# ProPrj_Motorcycle_Controller_2026-08-27.net
KiCad netlist of a schematic drawn in EasyEDA Pro
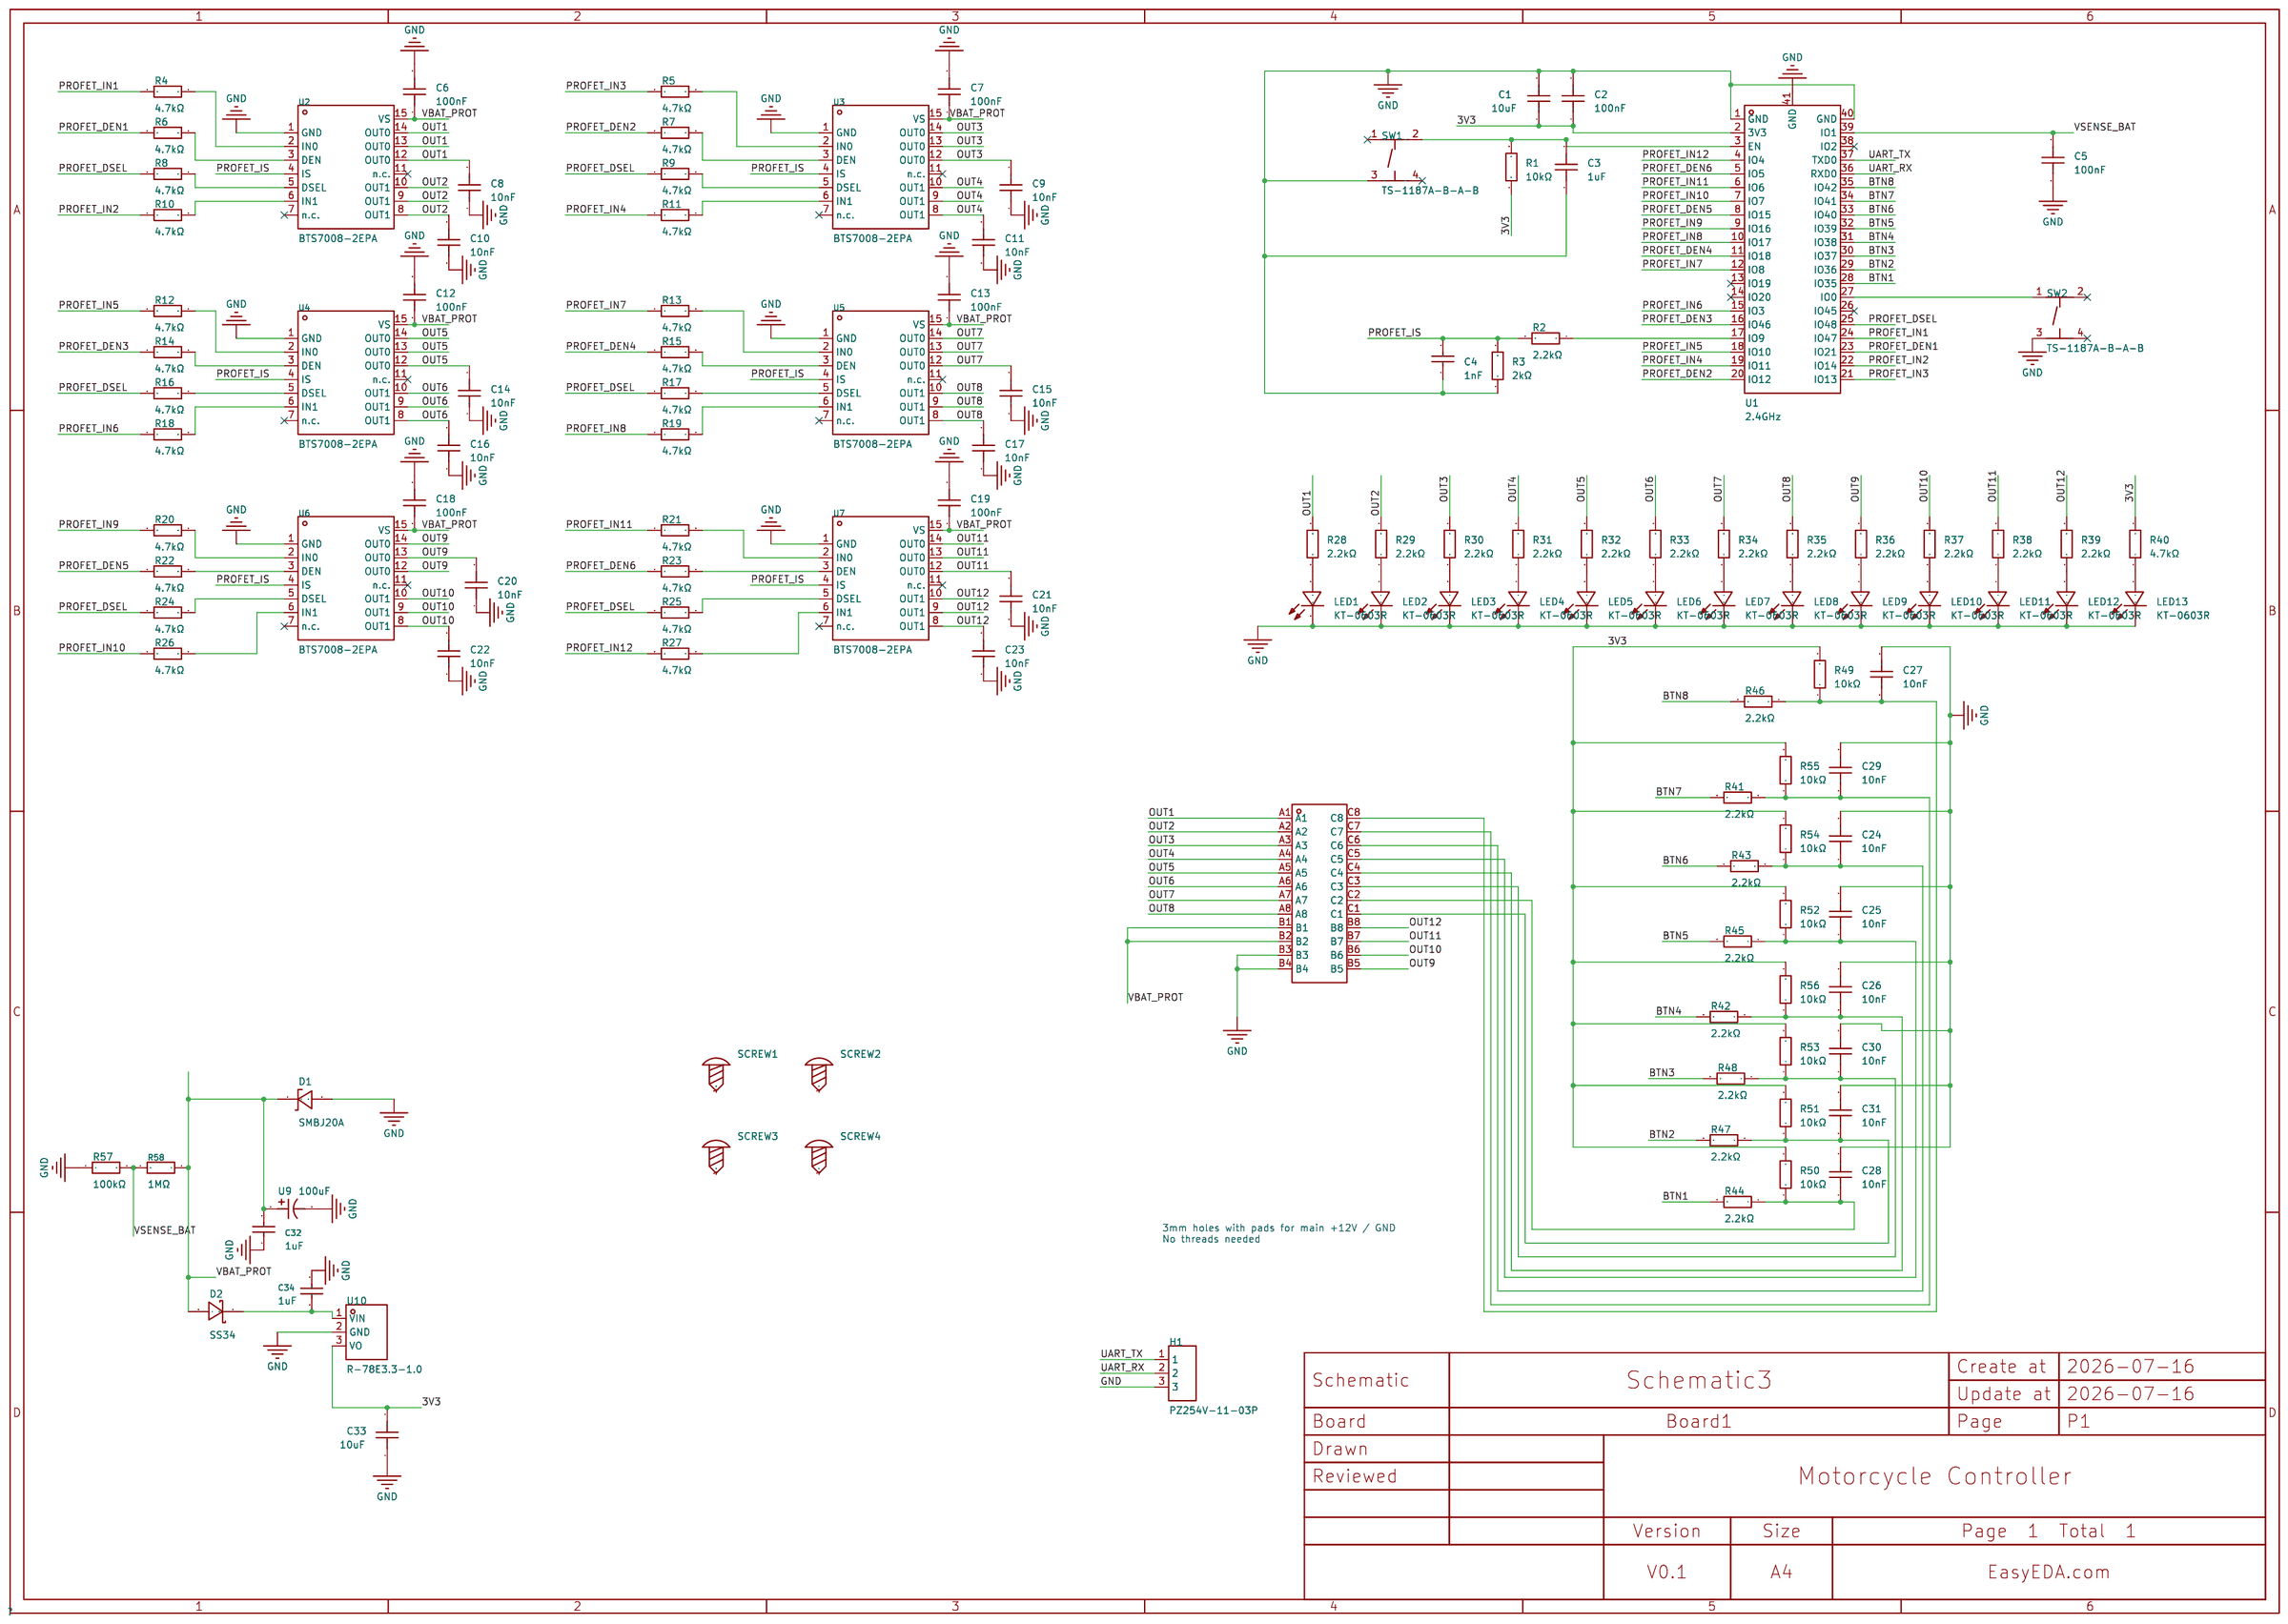
[diagram p0: schematic sheet]

(export (version "E")
  (design (tool "Eeschema 10.0.6"))
  (components
    (comp (ref "C1")
      (value "10uF")
      (footprint "easyedapro:C0603")
      (fields
        (field (name "Manufacturer Part") "CL10A106KP8NNNC")
        (field (name "Manufacturer") "SAMSUNG(三星)")
      )
      (libsource (lib "easyedapro") (part "CL10A106KP8NNNC"))
    )
    (comp (ref "C2")
      (value "100nF")
      (footprint "easyedapro:C0402")
      (fields
        (field (name "Manufacturer Part") "CL05B104KO5NNNC")
        (field (name "Manufacturer") "SAMSUNG(三星)")
      )
      (libsource (lib "easyedapro") (part "CL05B104KO5NNNC"))
    )
    (comp (ref "C3")
      (value "1uF")
      (footprint "easyedapro:C0402")
      (fields
        (field (name "Manufacturer Part") "CL05A105KA5NQNC")
        (field (name "Manufacturer") "SAMSUNG(三星)")
      )
      (libsource (lib "easyedapro") (part "CL05A105KA5NQNC"))
    )
    (comp (ref "C4")
      (value "1nF")
      (footprint "easyedapro:C0402")
      (fields (field (name "Manufacturer Part") "0402B102K500NT") (field (name "Manufacturer") "FH(风华)"))
      (libsource (lib "easyedapro") (part "0402B102K500NT"))
    )
    (comp (ref "C5")
      (value "100nF")
      (footprint "easyedapro:C0402")
      (fields
        (field (name "Manufacturer Part") "CL05B104KO5NNNC")
        (field (name "Manufacturer") "SAMSUNG(三星)")
      )
      (libsource (lib "easyedapro") (part "CL05B104KO5NNNC"))
    )
    (comp (ref "C6")
      (value "100nF")
      (footprint "easyedapro:C0603")
      (fields
        (field (name "Manufacturer Part") "CC0603KRX7R9BB104")
        (field (name "Manufacturer") "YAGEO(国巨)")
      )
      (libsource (lib "easyedapro") (part "CC0603KRX7R9BB104"))
    )
    (comp (ref "C7")
      (value "100nF")
      (footprint "easyedapro:C0603")
      (fields
        (field (name "Manufacturer Part") "CC0603KRX7R9BB104")
        (field (name "Manufacturer") "YAGEO(国巨)")
      )
      (libsource (lib "easyedapro") (part "CC0603KRX7R9BB104"))
    )
    (comp (ref "C8")
      (value "10nF")
      (footprint "easyedapro:C0603")
      (fields (field (name "Manufacturer Part") "0603B103K500NT") (field (name "Manufacturer") "FH(风华)"))
      (libsource (lib "easyedapro") (part "0603B103K500NT"))
    )
    (comp (ref "C9")
      (value "10nF")
      (footprint "easyedapro:C0603")
      (fields (field (name "Manufacturer Part") "0603B103K500NT") (field (name "Manufacturer") "FH(风华)"))
      (libsource (lib "easyedapro") (part "0603B103K500NT"))
    )
    (comp (ref "C10")
      (value "10nF")
      (footprint "easyedapro:C0603")
      (fields (field (name "Manufacturer Part") "0603B103K500NT") (field (name "Manufacturer") "FH(风华)"))
      (libsource (lib "easyedapro") (part "0603B103K500NT"))
    )
    (comp (ref "C11")
      (value "10nF")
      (footprint "easyedapro:C0603")
      (fields (field (name "Manufacturer Part") "0603B103K500NT") (field (name "Manufacturer") "FH(风华)"))
      (libsource (lib "easyedapro") (part "0603B103K500NT"))
    )
    (comp (ref "C12")
      (value "100nF")
      (footprint "easyedapro:C0603")
      (fields
        (field (name "Manufacturer Part") "CC0603KRX7R9BB104")
        (field (name "Manufacturer") "YAGEO(国巨)")
      )
      (libsource (lib "easyedapro") (part "CC0603KRX7R9BB104"))
    )
    (comp (ref "C13")
      (value "100nF")
      (footprint "easyedapro:C0603")
      (fields
        (field (name "Manufacturer Part") "CC0603KRX7R9BB104")
        (field (name "Manufacturer") "YAGEO(国巨)")
      )
      (libsource (lib "easyedapro") (part "CC0603KRX7R9BB104"))
    )
    (comp (ref "C14")
      (value "10nF")
      (footprint "easyedapro:C0603")
      (fields (field (name "Manufacturer Part") "0603B103K500NT") (field (name "Manufacturer") "FH(风华)"))
      (libsource (lib "easyedapro") (part "0603B103K500NT"))
    )
    (comp (ref "C15")
      (value "10nF")
      (footprint "easyedapro:C0603")
      (fields (field (name "Manufacturer Part") "0603B103K500NT") (field (name "Manufacturer") "FH(风华)"))
      (libsource (lib "easyedapro") (part "0603B103K500NT"))
    )
    (comp (ref "C16")
      (value "10nF")
      (footprint "easyedapro:C0603")
      (fields (field (name "Manufacturer Part") "0603B103K500NT") (field (name "Manufacturer") "FH(风华)"))
      (libsource (lib "easyedapro") (part "0603B103K500NT"))
    )
    (comp (ref "C17")
      (value "10nF")
      (footprint "easyedapro:C0603")
      (fields (field (name "Manufacturer Part") "0603B103K500NT") (field (name "Manufacturer") "FH(风华)"))
      (libsource (lib "easyedapro") (part "0603B103K500NT"))
    )
    (comp (ref "C18")
      (value "100nF")
      (footprint "easyedapro:C0603")
      (fields
        (field (name "Manufacturer Part") "CC0603KRX7R9BB104")
        (field (name "Manufacturer") "YAGEO(国巨)")
      )
      (libsource (lib "easyedapro") (part "CC0603KRX7R9BB104"))
    )
    (comp (ref "C19")
      (value "100nF")
      (footprint "easyedapro:C0603")
      (fields
        (field (name "Manufacturer Part") "CC0603KRX7R9BB104")
        (field (name "Manufacturer") "YAGEO(国巨)")
      )
      (libsource (lib "easyedapro") (part "CC0603KRX7R9BB104"))
    )
    (comp (ref "C20")
      (value "10nF")
      (footprint "easyedapro:C0603")
      (fields (field (name "Manufacturer Part") "0603B103K500NT") (field (name "Manufacturer") "FH(风华)"))
      (libsource (lib "easyedapro") (part "0603B103K500NT"))
    )
    (comp (ref "C21")
      (value "10nF")
      (footprint "easyedapro:C0603")
      (fields (field (name "Manufacturer Part") "0603B103K500NT") (field (name "Manufacturer") "FH(风华)"))
      (libsource (lib "easyedapro") (part "0603B103K500NT"))
    )
    (comp (ref "C22")
      (value "10nF")
      (footprint "easyedapro:C0603")
      (fields (field (name "Manufacturer Part") "0603B103K500NT") (field (name "Manufacturer") "FH(风华)"))
      (libsource (lib "easyedapro") (part "0603B103K500NT"))
    )
    (comp (ref "C23")
      (value "10nF")
      (footprint "easyedapro:C0603")
      (fields (field (name "Manufacturer Part") "0603B103K500NT") (field (name "Manufacturer") "FH(风华)"))
      (libsource (lib "easyedapro") (part "0603B103K500NT"))
    )
    (comp (ref "C24")
      (value "10nF")
      (footprint "easyedapro:C0603")
      (fields (field (name "Manufacturer Part") "0603B103K500NT") (field (name "Manufacturer") "FH(风华)"))
      (libsource (lib "easyedapro") (part "0603B103K500NT"))
    )
    (comp (ref "C25")
      (value "10nF")
      (footprint "easyedapro:C0603")
      (fields (field (name "Manufacturer Part") "0603B103K500NT") (field (name "Manufacturer") "FH(风华)"))
      (libsource (lib "easyedapro") (part "0603B103K500NT"))
    )
    (comp (ref "C26")
      (value "10nF")
      (footprint "easyedapro:C0603")
      (fields (field (name "Manufacturer Part") "0603B103K500NT") (field (name "Manufacturer") "FH(风华)"))
      (libsource (lib "easyedapro") (part "0603B103K500NT"))
    )
    (comp (ref "C27")
      (value "10nF")
      (footprint "easyedapro:C0603")
      (fields (field (name "Manufacturer Part") "0603B103K500NT") (field (name "Manufacturer") "FH(风华)"))
      (libsource (lib "easyedapro") (part "0603B103K500NT"))
    )
    (comp (ref "C28")
      (value "10nF")
      (footprint "easyedapro:C0603")
      (fields (field (name "Manufacturer Part") "0603B103K500NT") (field (name "Manufacturer") "FH(风华)"))
      (libsource (lib "easyedapro") (part "0603B103K500NT"))
    )
    (comp (ref "C29")
      (value "10nF")
      (footprint "easyedapro:C0603")
      (fields (field (name "Manufacturer Part") "0603B103K500NT") (field (name "Manufacturer") "FH(风华)"))
      (libsource (lib "easyedapro") (part "0603B103K500NT"))
    )
    (comp (ref "C30")
      (value "10nF")
      (footprint "easyedapro:C0603")
      (fields (field (name "Manufacturer Part") "0603B103K500NT") (field (name "Manufacturer") "FH(风华)"))
      (libsource (lib "easyedapro") (part "0603B103K500NT"))
    )
    (comp (ref "C31")
      (value "10nF")
      (footprint "easyedapro:C0603")
      (fields (field (name "Manufacturer Part") "0603B103K500NT") (field (name "Manufacturer") "FH(风华)"))
      (libsource (lib "easyedapro") (part "0603B103K500NT"))
    )
    (comp (ref "C32")
      (value "1uF")
      (footprint "easyedapro:C0805")
      (fields
        (field (name "Manufacturer Part") "CL21B105KBFNNNE")
        (field (name "Manufacturer") "SAMSUNG(三星)")
      )
      (libsource (lib "easyedapro") (part "CL21B105KBFNNNE"))
    )
    (comp (ref "C33")
      (value "10uF")
      (footprint "easyedapro:C0603")
      (fields
        (field (name "Manufacturer Part") "CL10A106KP8NNNC")
        (field (name "Manufacturer") "SAMSUNG(三星)")
      )
      (libsource (lib "easyedapro") (part "CL10A106KP8NNNC"))
    )
    (comp (ref "C34")
      (value "1uF")
      (footprint "easyedapro:C0805")
      (fields
        (field (name "Manufacturer Part") "CL21B105KBFNNNE")
        (field (name "Manufacturer") "SAMSUNG(三星)")
      )
      (libsource (lib "easyedapro") (part "CL21B105KBFNNNE"))
    )
    (comp (ref "CN3")
      (value "HCCPHPE24BKA90F")
      (footprint "easyedapro:CONN-TH_HCCPHPE24BKA90F")
      (fields (field (name "Manufacturer") "Aptiv(Delphi)"))
      (libsource (lib "easyedapro") (part "HCCPHPE24BKA90F_C5349068"))
    )
    (comp (ref "D1")
      (value "SMBJ20A")
      (footprint "easyedapro:SMB_L4.6-W3.6-LS5.3-RD")
      (fields (field (name "Manufacturer") "MDD(辰达半导体)"))
      (libsource (lib "easyedapro") (part "SMBJ20A_C364296"))
    )
    (comp (ref "D2")
      (value "SS34")
      (footprint "easyedapro:SMA_L4.3-W2.6-LS5.2-RD")
      (fields (field (name "Manufacturer") "MDD(辰达半导体)"))
      (libsource (lib "easyedapro") (part "SS34_C8678"))
    )
    (comp (ref "H1")
      (value "PZ254V-11-03P")
      (footprint "easyedapro:HDR-TH_3P-P2.54-V-M_PZ254V-11-03P")
      (fields (field (name "Manufacturer") "XFCN(兴飞)"))
      (libsource (lib "easyedapro") (part "PZ254V-11-03P_C2937625"))
    )
    (comp (ref "LED1")
      (value "KT-0603R")
      (footprint "easyedapro:LED-SMD_L1.6-W0.8-R-RD")
      (fields (field (name "Manufacturer") "KENTO"))
      (libsource (lib "easyedapro") (part "KT-0603R"))
    )
    (comp (ref "LED2")
      (value "KT-0603R")
      (footprint "easyedapro:LED-SMD_L1.6-W0.8-R-RD")
      (fields (field (name "Manufacturer") "KENTO"))
      (libsource (lib "easyedapro") (part "KT-0603R"))
    )
    (comp (ref "LED3")
      (value "KT-0603R")
      (footprint "easyedapro:LED-SMD_L1.6-W0.8-R-RD")
      (fields (field (name "Manufacturer") "KENTO"))
      (libsource (lib "easyedapro") (part "KT-0603R"))
    )
    (comp (ref "LED4")
      (value "KT-0603R")
      (footprint "easyedapro:LED-SMD_L1.6-W0.8-R-RD")
      (fields (field (name "Manufacturer") "KENTO"))
      (libsource (lib "easyedapro") (part "KT-0603R"))
    )
    (comp (ref "LED5")
      (value "KT-0603R")
      (footprint "easyedapro:LED-SMD_L1.6-W0.8-R-RD")
      (fields (field (name "Manufacturer") "KENTO"))
      (libsource (lib "easyedapro") (part "KT-0603R"))
    )
    (comp (ref "LED6")
      (value "KT-0603R")
      (footprint "easyedapro:LED-SMD_L1.6-W0.8-R-RD")
      (fields (field (name "Manufacturer") "KENTO"))
      (libsource (lib "easyedapro") (part "KT-0603R"))
    )
    (comp (ref "LED7")
      (value "KT-0603R")
      (footprint "easyedapro:LED-SMD_L1.6-W0.8-R-RD")
      (fields (field (name "Manufacturer") "KENTO"))
      (libsource (lib "easyedapro") (part "KT-0603R"))
    )
    (comp (ref "LED8")
      (value "KT-0603R")
      (footprint "easyedapro:LED-SMD_L1.6-W0.8-R-RD")
      (fields (field (name "Manufacturer") "KENTO"))
      (libsource (lib "easyedapro") (part "KT-0603R"))
    )
    (comp (ref "LED9")
      (value "KT-0603R")
      (footprint "easyedapro:LED-SMD_L1.6-W0.8-R-RD")
      (fields (field (name "Manufacturer") "KENTO"))
      (libsource (lib "easyedapro") (part "KT-0603R"))
    )
    (comp (ref "LED10")
      (value "KT-0603R")
      (footprint "easyedapro:LED-SMD_L1.6-W0.8-R-RD")
      (fields (field (name "Manufacturer") "KENTO"))
      (libsource (lib "easyedapro") (part "KT-0603R"))
    )
    (comp (ref "LED11")
      (value "KT-0603R")
      (footprint "easyedapro:LED-SMD_L1.6-W0.8-R-RD")
      (fields (field (name "Manufacturer") "KENTO"))
      (libsource (lib "easyedapro") (part "KT-0603R"))
    )
    (comp (ref "LED12")
      (value "KT-0603R")
      (footprint "easyedapro:LED-SMD_L1.6-W0.8-R-RD")
      (fields (field (name "Manufacturer") "KENTO"))
      (libsource (lib "easyedapro") (part "KT-0603R"))
    )
    (comp (ref "LED13")
      (value "KT-0603R")
      (footprint "easyedapro:LED-SMD_L1.6-W0.8-R-RD")
      (fields (field (name "Manufacturer") "KENTO"))
      (libsource (lib "easyedapro") (part "KT-0603R"))
    )
    (comp (ref "R1")
      (value "10kΩ")
      (footprint "easyedapro:R0402")
      (fields (field (name "Manufacturer Part") "RC0402FR-0710KL") (field (name "Manufacturer") "YAGEO(国巨)"))
      (libsource (lib "easyedapro") (part "RC0402FR-0710KL"))
    )
    (comp (ref "R2")
      (value "2.2kΩ")
      (footprint "easyedapro:R0603")
      (fields
        (field (name "Manufacturer Part") "0603WAF2201T5E")
        (field (name "Manufacturer") "UNI-ROYAL(厚声)")
      )
      (libsource (lib "easyedapro") (part "0603WAF2201T5E"))
    )
    (comp (ref "R3")
      (value "2kΩ")
      (footprint "easyedapro:R0603")
      (fields
        (field (name "Manufacturer Part") "0603WAF2001T5E")
        (field (name "Manufacturer") "UNI-ROYAL(厚声)")
      )
      (libsource (lib "easyedapro") (part "0603WAF2001T5E"))
    )
    (comp (ref "R4")
      (value "4.7kΩ")
      (footprint "easyedapro:R0603")
      (fields
        (field (name "Manufacturer Part") "0603WAF4701T5E")
        (field (name "Manufacturer") "UNI-ROYAL(厚声)")
      )
      (libsource (lib "easyedapro") (part "0603WAF4701T5E"))
    )
    (comp (ref "R5")
      (value "4.7kΩ")
      (footprint "easyedapro:R0603")
      (fields
        (field (name "Manufacturer Part") "0603WAF4701T5E")
        (field (name "Manufacturer") "UNI-ROYAL(厚声)")
      )
      (libsource (lib "easyedapro") (part "0603WAF4701T5E"))
    )
    (comp (ref "R6")
      (value "4.7kΩ")
      (footprint "easyedapro:R0603")
      (fields
        (field (name "Manufacturer Part") "0603WAF4701T5E")
        (field (name "Manufacturer") "UNI-ROYAL(厚声)")
      )
      (libsource (lib "easyedapro") (part "0603WAF4701T5E"))
    )
    (comp (ref "R7")
      (value "4.7kΩ")
      (footprint "easyedapro:R0603")
      (fields
        (field (name "Manufacturer Part") "0603WAF4701T5E")
        (field (name "Manufacturer") "UNI-ROYAL(厚声)")
      )
      (libsource (lib "easyedapro") (part "0603WAF4701T5E"))
    )
    (comp (ref "R8")
      (value "4.7kΩ")
      (footprint "easyedapro:R0603")
      (fields
        (field (name "Manufacturer Part") "0603WAF4701T5E")
        (field (name "Manufacturer") "UNI-ROYAL(厚声)")
      )
      (libsource (lib "easyedapro") (part "0603WAF4701T5E"))
    )
    (comp (ref "R9")
      (value "4.7kΩ")
      (footprint "easyedapro:R0603")
      (fields
        (field (name "Manufacturer Part") "0603WAF4701T5E")
        (field (name "Manufacturer") "UNI-ROYAL(厚声)")
      )
      (libsource (lib "easyedapro") (part "0603WAF4701T5E"))
    )
    (comp (ref "R10")
      (value "4.7kΩ")
      (footprint "easyedapro:R0603")
      (fields
        (field (name "Manufacturer Part") "0603WAF4701T5E")
        (field (name "Manufacturer") "UNI-ROYAL(厚声)")
      )
      (libsource (lib "easyedapro") (part "0603WAF4701T5E"))
    )
    (comp (ref "R11")
      (value "4.7kΩ")
      (footprint "easyedapro:R0603")
      (fields
        (field (name "Manufacturer Part") "0603WAF4701T5E")
        (field (name "Manufacturer") "UNI-ROYAL(厚声)")
      )
      (libsource (lib "easyedapro") (part "0603WAF4701T5E"))
    )
    (comp (ref "R12")
      (value "4.7kΩ")
      (footprint "easyedapro:R0603")
      (fields
        (field (name "Manufacturer Part") "0603WAF4701T5E")
        (field (name "Manufacturer") "UNI-ROYAL(厚声)")
      )
      (libsource (lib "easyedapro") (part "0603WAF4701T5E"))
    )
    (comp (ref "R13")
      (value "4.7kΩ")
      (footprint "easyedapro:R0603")
      (fields
        (field (name "Manufacturer Part") "0603WAF4701T5E")
        (field (name "Manufacturer") "UNI-ROYAL(厚声)")
      )
      (libsource (lib "easyedapro") (part "0603WAF4701T5E"))
    )
    (comp (ref "R14")
      (value "4.7kΩ")
      (footprint "easyedapro:R0603")
      (fields
        (field (name "Manufacturer Part") "0603WAF4701T5E")
        (field (name "Manufacturer") "UNI-ROYAL(厚声)")
      )
      (libsource (lib "easyedapro") (part "0603WAF4701T5E"))
    )
    (comp (ref "R15")
      (value "4.7kΩ")
      (footprint "easyedapro:R0603")
      (fields
        (field (name "Manufacturer Part") "0603WAF4701T5E")
        (field (name "Manufacturer") "UNI-ROYAL(厚声)")
      )
      (libsource (lib "easyedapro") (part "0603WAF4701T5E"))
    )
    (comp (ref "R16")
      (value "4.7kΩ")
      (footprint "easyedapro:R0603")
      (fields
        (field (name "Manufacturer Part") "0603WAF4701T5E")
        (field (name "Manufacturer") "UNI-ROYAL(厚声)")
      )
      (libsource (lib "easyedapro") (part "0603WAF4701T5E"))
    )
    (comp (ref "R17")
      (value "4.7kΩ")
      (footprint "easyedapro:R0603")
      (fields
        (field (name "Manufacturer Part") "0603WAF4701T5E")
        (field (name "Manufacturer") "UNI-ROYAL(厚声)")
      )
      (libsource (lib "easyedapro") (part "0603WAF4701T5E"))
    )
    (comp (ref "R18")
      (value "4.7kΩ")
      (footprint "easyedapro:R0603")
      (fields
        (field (name "Manufacturer Part") "0603WAF4701T5E")
        (field (name "Manufacturer") "UNI-ROYAL(厚声)")
      )
      (libsource (lib "easyedapro") (part "0603WAF4701T5E"))
    )
    (comp (ref "R19")
      (value "4.7kΩ")
      (footprint "easyedapro:R0603")
      (fields
        (field (name "Manufacturer Part") "0603WAF4701T5E")
        (field (name "Manufacturer") "UNI-ROYAL(厚声)")
      )
      (libsource (lib "easyedapro") (part "0603WAF4701T5E"))
    )
    (comp (ref "R20")
      (value "4.7kΩ")
      (footprint "easyedapro:R0603")
      (fields
        (field (name "Manufacturer Part") "0603WAF4701T5E")
        (field (name "Manufacturer") "UNI-ROYAL(厚声)")
      )
      (libsource (lib "easyedapro") (part "0603WAF4701T5E"))
    )
    (comp (ref "R21")
      (value "4.7kΩ")
      (footprint "easyedapro:R0603")
      (fields
        (field (name "Manufacturer Part") "0603WAF4701T5E")
        (field (name "Manufacturer") "UNI-ROYAL(厚声)")
      )
      (libsource (lib "easyedapro") (part "0603WAF4701T5E"))
    )
    (comp (ref "R22")
      (value "4.7kΩ")
      (footprint "easyedapro:R0603")
      (fields
        (field (name "Manufacturer Part") "0603WAF4701T5E")
        (field (name "Manufacturer") "UNI-ROYAL(厚声)")
      )
      (libsource (lib "easyedapro") (part "0603WAF4701T5E"))
    )
    (comp (ref "R23")
      (value "4.7kΩ")
      (footprint "easyedapro:R0603")
      (fields
        (field (name "Manufacturer Part") "0603WAF4701T5E")
        (field (name "Manufacturer") "UNI-ROYAL(厚声)")
      )
      (libsource (lib "easyedapro") (part "0603WAF4701T5E"))
    )
    (comp (ref "R24")
      (value "4.7kΩ")
      (footprint "easyedapro:R0603")
      (fields
        (field (name "Manufacturer Part") "0603WAF4701T5E")
        (field (name "Manufacturer") "UNI-ROYAL(厚声)")
      )
      (libsource (lib "easyedapro") (part "0603WAF4701T5E"))
    )
    (comp (ref "R25")
      (value "4.7kΩ")
      (footprint "easyedapro:R0603")
      (fields
        (field (name "Manufacturer Part") "0603WAF4701T5E")
        (field (name "Manufacturer") "UNI-ROYAL(厚声)")
      )
      (libsource (lib "easyedapro") (part "0603WAF4701T5E"))
    )
    (comp (ref "R26")
      (value "4.7kΩ")
      (footprint "easyedapro:R0603")
      (fields
        (field (name "Manufacturer Part") "0603WAF4701T5E")
        (field (name "Manufacturer") "UNI-ROYAL(厚声)")
      )
      (libsource (lib "easyedapro") (part "0603WAF4701T5E"))
    )
    (comp (ref "R27")
      (value "4.7kΩ")
      (footprint "easyedapro:R0603")
      (fields
        (field (name "Manufacturer Part") "0603WAF4701T5E")
        (field (name "Manufacturer") "UNI-ROYAL(厚声)")
      )
      (libsource (lib "easyedapro") (part "0603WAF4701T5E"))
    )
    (comp (ref "R28")
      (value "2.2kΩ")
      (footprint "easyedapro:R0603")
      (fields
        (field (name "Manufacturer Part") "0603WAF2201T5E")
        (field (name "Manufacturer") "UNI-ROYAL(厚声)")
      )
      (libsource (lib "easyedapro") (part "0603WAF2201T5E"))
    )
    (comp (ref "R29")
      (value "2.2kΩ")
      (footprint "easyedapro:R0603")
      (fields
        (field (name "Manufacturer Part") "0603WAF2201T5E")
        (field (name "Manufacturer") "UNI-ROYAL(厚声)")
      )
      (libsource (lib "easyedapro") (part "0603WAF2201T5E"))
    )
    (comp (ref "R30")
      (value "2.2kΩ")
      (footprint "easyedapro:R0603")
      (fields
        (field (name "Manufacturer Part") "0603WAF2201T5E")
        (field (name "Manufacturer") "UNI-ROYAL(厚声)")
      )
      (libsource (lib "easyedapro") (part "0603WAF2201T5E"))
    )
    (comp (ref "R31")
      (value "2.2kΩ")
      (footprint "easyedapro:R0603")
      (fields
        (field (name "Manufacturer Part") "0603WAF2201T5E")
        (field (name "Manufacturer") "UNI-ROYAL(厚声)")
      )
      (libsource (lib "easyedapro") (part "0603WAF2201T5E"))
    )
    (comp (ref "R32")
      (value "2.2kΩ")
      (footprint "easyedapro:R0603")
      (fields
        (field (name "Manufacturer Part") "0603WAF2201T5E")
        (field (name "Manufacturer") "UNI-ROYAL(厚声)")
      )
      (libsource (lib "easyedapro") (part "0603WAF2201T5E"))
    )
    (comp (ref "R33")
      (value "2.2kΩ")
      (footprint "easyedapro:R0603")
      (fields
        (field (name "Manufacturer Part") "0603WAF2201T5E")
        (field (name "Manufacturer") "UNI-ROYAL(厚声)")
      )
      (libsource (lib "easyedapro") (part "0603WAF2201T5E"))
    )
    (comp (ref "R34")
      (value "2.2kΩ")
      (footprint "easyedapro:R0603")
      (fields
        (field (name "Manufacturer Part") "0603WAF2201T5E")
        (field (name "Manufacturer") "UNI-ROYAL(厚声)")
      )
      (libsource (lib "easyedapro") (part "0603WAF2201T5E"))
    )
    (comp (ref "R35")
      (value "2.2kΩ")
      (footprint "easyedapro:R0603")
      (fields
        (field (name "Manufacturer Part") "0603WAF2201T5E")
        (field (name "Manufacturer") "UNI-ROYAL(厚声)")
      )
      (libsource (lib "easyedapro") (part "0603WAF2201T5E"))
    )
    (comp (ref "R36")
      (value "2.2kΩ")
      (footprint "easyedapro:R0603")
      (fields
        (field (name "Manufacturer Part") "0603WAF2201T5E")
        (field (name "Manufacturer") "UNI-ROYAL(厚声)")
      )
      (libsource (lib "easyedapro") (part "0603WAF2201T5E"))
    )
    (comp (ref "R37")
      (value "2.2kΩ")
      (footprint "easyedapro:R0603")
      (fields
        (field (name "Manufacturer Part") "0603WAF2201T5E")
        (field (name "Manufacturer") "UNI-ROYAL(厚声)")
      )
      (libsource (lib "easyedapro") (part "0603WAF2201T5E"))
    )
    (comp (ref "R38")
      (value "2.2kΩ")
      (footprint "easyedapro:R0603")
      (fields
        (field (name "Manufacturer Part") "0603WAF2201T5E")
        (field (name "Manufacturer") "UNI-ROYAL(厚声)")
      )
      (libsource (lib "easyedapro") (part "0603WAF2201T5E"))
    )
    (comp (ref "R39")
      (value "2.2kΩ")
      (footprint "easyedapro:R0603")
      (fields
        (field (name "Manufacturer Part") "0603WAF2201T5E")
        (field (name "Manufacturer") "UNI-ROYAL(厚声)")
      )
      (libsource (lib "easyedapro") (part "0603WAF2201T5E"))
    )
    (comp (ref "R40")
      (value "4.7kΩ")
      (footprint "easyedapro:R0603")
      (fields
        (field (name "Manufacturer Part") "0603WAF4701T5E")
        (field (name "Manufacturer") "UNI-ROYAL(厚声)")
      )
      (libsource (lib "easyedapro") (part "0603WAF4701T5E"))
    )
    (comp (ref "R41")
      (value "2.2kΩ")
      (footprint "easyedapro:R0603")
      (fields
        (field (name "Manufacturer Part") "0603WAF2201T5E")
        (field (name "Manufacturer") "UNI-ROYAL(厚声)")
      )
      (libsource (lib "easyedapro") (part "0603WAF2201T5E"))
    )
    (comp (ref "R42")
      (value "2.2kΩ")
      (footprint "easyedapro:R0603")
      (fields
        (field (name "Manufacturer Part") "0603WAF2201T5E")
        (field (name "Manufacturer") "UNI-ROYAL(厚声)")
      )
      (libsource (lib "easyedapro") (part "0603WAF2201T5E"))
    )
    (comp (ref "R43")
      (value "2.2kΩ")
      (footprint "easyedapro:R0603")
      (fields
        (field (name "Manufacturer Part") "0603WAF2201T5E")
        (field (name "Manufacturer") "UNI-ROYAL(厚声)")
      )
      (libsource (lib "easyedapro") (part "0603WAF2201T5E"))
    )
    (comp (ref "R44")
      (value "2.2kΩ")
      (footprint "easyedapro:R0603")
      (fields
        (field (name "Manufacturer Part") "0603WAF2201T5E")
        (field (name "Manufacturer") "UNI-ROYAL(厚声)")
      )
      (libsource (lib "easyedapro") (part "0603WAF2201T5E"))
    )
    (comp (ref "R45")
      (value "2.2kΩ")
      (footprint "easyedapro:R0603")
      (fields
        (field (name "Manufacturer Part") "0603WAF2201T5E")
        (field (name "Manufacturer") "UNI-ROYAL(厚声)")
      )
      (libsource (lib "easyedapro") (part "0603WAF2201T5E"))
    )
    (comp (ref "R46")
      (value "2.2kΩ")
      (footprint "easyedapro:R0603")
      (fields
        (field (name "Manufacturer Part") "0603WAF2201T5E")
        (field (name "Manufacturer") "UNI-ROYAL(厚声)")
      )
      (libsource (lib "easyedapro") (part "0603WAF2201T5E"))
    )
    (comp (ref "R47")
      (value "2.2kΩ")
      (footprint "easyedapro:R0603")
      (fields
        (field (name "Manufacturer Part") "0603WAF2201T5E")
        (field (name "Manufacturer") "UNI-ROYAL(厚声)")
      )
      (libsource (lib "easyedapro") (part "0603WAF2201T5E"))
    )
    (comp (ref "R48")
      (value "2.2kΩ")
      (footprint "easyedapro:R0603")
      (fields
        (field (name "Manufacturer Part") "0603WAF2201T5E")
        (field (name "Manufacturer") "UNI-ROYAL(厚声)")
      )
      (libsource (lib "easyedapro") (part "0603WAF2201T5E"))
    )
    (comp (ref "R49")
      (value "10kΩ")
      (footprint "easyedapro:R0402")
      (fields (field (name "Manufacturer Part") "RC0402FR-0710KL") (field (name "Manufacturer") "YAGEO(国巨)"))
      (libsource (lib "easyedapro") (part "RC0402FR-0710KL"))
    )
    (comp (ref "R50")
      (value "10kΩ")
      (footprint "easyedapro:R0402")
      (fields (field (name "Manufacturer Part") "RC0402FR-0710KL") (field (name "Manufacturer") "YAGEO(国巨)"))
      (libsource (lib "easyedapro") (part "RC0402FR-0710KL"))
    )
    (comp (ref "R51")
      (value "10kΩ")
      (footprint "easyedapro:R0402")
      (fields (field (name "Manufacturer Part") "RC0402FR-0710KL") (field (name "Manufacturer") "YAGEO(国巨)"))
      (libsource (lib "easyedapro") (part "RC0402FR-0710KL"))
    )
    (comp (ref "R52")
      (value "10kΩ")
      (footprint "easyedapro:R0402")
      (fields (field (name "Manufacturer Part") "RC0402FR-0710KL") (field (name "Manufacturer") "YAGEO(国巨)"))
      (libsource (lib "easyedapro") (part "RC0402FR-0710KL"))
    )
    (comp (ref "R53")
      (value "10kΩ")
      (footprint "easyedapro:R0402")
      (fields (field (name "Manufacturer Part") "RC0402FR-0710KL") (field (name "Manufacturer") "YAGEO(国巨)"))
      (libsource (lib "easyedapro") (part "RC0402FR-0710KL"))
    )
    (comp (ref "R54")
      (value "10kΩ")
      (footprint "easyedapro:R0402")
      (fields (field (name "Manufacturer Part") "RC0402FR-0710KL") (field (name "Manufacturer") "YAGEO(国巨)"))
      (libsource (lib "easyedapro") (part "RC0402FR-0710KL"))
    )
    (comp (ref "R55")
      (value "10kΩ")
      (footprint "easyedapro:R0402")
      (fields (field (name "Manufacturer Part") "RC0402FR-0710KL") (field (name "Manufacturer") "YAGEO(国巨)"))
      (libsource (lib "easyedapro") (part "RC0402FR-0710KL"))
    )
    (comp (ref "R56")
      (value "10kΩ")
      (footprint "easyedapro:R0402")
      (fields (field (name "Manufacturer Part") "RC0402FR-0710KL") (field (name "Manufacturer") "YAGEO(国巨)"))
      (libsource (lib "easyedapro") (part "RC0402FR-0710KL"))
    )
    (comp (ref "R57")
      (value "100kΩ")
      (footprint "easyedapro:R0603")
      (fields
        (field (name "Manufacturer Part") "0603WAF1003T5E")
        (field (name "Manufacturer") "UNI-ROYAL(厚声)")
      )
      (libsource (lib "easyedapro") (part "0603WAF1003T5E"))
    )
    (comp (ref "R58")
      (value "1MΩ")
      (footprint "easyedapro:R0603")
      (fields
        (field (name "Manufacturer Part") "0603WAF1004T5E")
        (field (name "Manufacturer") "UNI-ROYAL(厚声)")
      )
      (libsource (lib "easyedapro") (part "0603WAF1004T5E"))
    )
    (comp (ref "SCREW1")
      (value "~")
      (footprint "easyedapro:Screw-Hole-M3")
      (libsource (lib "easyedapro") (part "Screw-Hole"))
    )
    (comp (ref "SCREW2")
      (value "~")
      (footprint "easyedapro:Screw-Hole-M3")
      (libsource (lib "easyedapro") (part "Screw-Hole"))
    )
    (comp (ref "SCREW3")
      (value "~")
      (footprint "easyedapro:Screw-Hole-M3")
      (libsource (lib "easyedapro") (part "Screw-Hole"))
    )
    (comp (ref "SCREW4")
      (value "~")
      (footprint "easyedapro:Screw-Hole-M3")
      (libsource (lib "easyedapro") (part "Screw-Hole"))
    )
    (comp (ref "SW1")
      (value "TS-1187A-B-A-B")
      (footprint "easyedapro:SW-SMD_4P-L5.1-W5.1-P3.70-LS6.5-TL_H1.5")
      (fields (field (name "Manufacturer") "XKB Connection(中国星坤)"))
      (libsource (lib "easyedapro") (part "TS-1187A-B-A-B"))
    )
    (comp (ref "SW2")
      (value "TS-1187A-B-A-B")
      (footprint "easyedapro:SW-SMD_4P-L5.1-W5.1-P3.70-LS6.5-TL_H1.5")
      (fields (field (name "Manufacturer") "XKB Connection(中国星坤)"))
      (libsource (lib "easyedapro") (part "TS-1187A-B-A-B"))
    )
    (comp (ref "U1")
      (value "2.4GHz")
      (footprint "easyedapro:WIFIM-SMD_ESP32-S3-WROOM-1-N8")
      (fields
        (field (name "Manufacturer Part") "ESP32-S3-WROOM-1-N4")
        (field (name "Manufacturer") "ESPRESSIF(乐鑫)")
      )
      (libsource (lib "easyedapro") (part "ESP32-S3-WROOM-1-N4"))
    )
    (comp (ref "U2")
      (value "BTS7008-2EPA")
      (footprint "easyedapro:PG-TSDSO-14_L4.9-W3.9-P0.65-LS6.0-BL-EP")
      (fields (field (name "Manufacturer") "Infineon(英飞凌)"))
      (libsource (lib "easyedapro") (part "BTS7008-2EPA"))
    )
    (comp (ref "U3")
      (value "BTS7008-2EPA")
      (footprint "easyedapro:PG-TSDSO-14_L4.9-W3.9-P0.65-LS6.0-BL-EP")
      (fields (field (name "Manufacturer") "Infineon(英飞凌)"))
      (libsource (lib "easyedapro") (part "BTS7008-2EPA"))
    )
    (comp (ref "U4")
      (value "BTS7008-2EPA")
      (footprint "easyedapro:PG-TSDSO-14_L4.9-W3.9-P0.65-LS6.0-BL-EP")
      (fields (field (name "Manufacturer") "Infineon(英飞凌)"))
      (libsource (lib "easyedapro") (part "BTS7008-2EPA"))
    )
    (comp (ref "U5")
      (value "BTS7008-2EPA")
      (footprint "easyedapro:PG-TSDSO-14_L4.9-W3.9-P0.65-LS6.0-BL-EP")
      (fields (field (name "Manufacturer") "Infineon(英飞凌)"))
      (libsource (lib "easyedapro") (part "BTS7008-2EPA"))
    )
    (comp (ref "U6")
      (value "BTS7008-2EPA")
      (footprint "easyedapro:PG-TSDSO-14_L4.9-W3.9-P0.65-LS6.0-BL-EP")
      (fields (field (name "Manufacturer") "Infineon(英飞凌)"))
      (libsource (lib "easyedapro") (part "BTS7008-2EPA"))
    )
    (comp (ref "U7")
      (value "BTS7008-2EPA")
      (footprint "easyedapro:PG-TSDSO-14_L4.9-W3.9-P0.65-LS6.0-BL-EP")
      (fields (field (name "Manufacturer") "Infineon(英飞凌)"))
      (libsource (lib "easyedapro") (part "BTS7008-2EPA"))
    )
    (comp (ref "U9")
      (value "100uF")
      (footprint "easyedapro:CAP-SMD_BD8.0-L8.3-W8.3-LS9.1-FD")
      (fields
        (field (name "Manufacturer Part") "RVT1H101M0810 100UF 50V")
        (field (name "Manufacturer") "DMBJ(振宝佳)")
      )
      (libsource (lib "easyedapro") (part "RVT1H101M0810 100UF 50V"))
    )
    (comp (ref "U10")
      (value "R-78E3.3-1.0")
      (footprint "easyedapro:PWRM-TH_R-78EXX-1.0")
      (fields (field (name "Manufacturer") "YLPTEC(易川)"))
      (libsource (lib "easyedapro") (part "R-78E3.3-1.0"))
    )
  )
  (nets
    (net (code "1") (name "/3V3") (class "Default")
      (node (ref "C1") (pin "1") (pinfunction "1_1") (pintype "unspecified"))
      (node (ref "C2") (pin "1") (pinfunction "1_1") (pintype "unspecified"))
      (node (ref "C33") (pin "2") (pinfunction "2_2") (pintype "unspecified"))
      (node (ref "R1") (pin "1") (pinfunction "1_1") (pintype "input"))
      (node (ref "R40") (pin "2") (pinfunction "2_2") (pintype "input"))
      (node (ref "R49") (pin "2") (pinfunction "2_2") (pintype "input"))
      (node (ref "R50") (pin "2") (pinfunction "2_2") (pintype "input"))
      (node (ref "R51") (pin "2") (pinfunction "2_2") (pintype "input"))
      (node (ref "R52") (pin "2") (pinfunction "2_2") (pintype "input"))
      (node (ref "R53") (pin "2") (pinfunction "2_2") (pintype "input"))
      (node (ref "R54") (pin "2") (pinfunction "2_2") (pintype "input"))
      (node (ref "R55") (pin "2") (pinfunction "2_2") (pintype "input"))
      (node (ref "R56") (pin "2") (pinfunction "2_2") (pintype "input"))
      (node (ref "U1") (pin "2") (pinfunction "3V3_2") (pintype "unspecified"))
      (node (ref "U10") (pin "3") (pinfunction "VO_3") (pintype "unspecified"))
    )
    (net (code "2") (name "/BTN1") (class "Default")
      (node (ref "R44") (pin "2") (pinfunction "2_2") (pintype "input"))
      (node (ref "U1") (pin "28") (pinfunction "IO35_28") (pintype "unspecified"))
    )
    (net (code "3") (name "/BTN2") (class "Default")
      (node (ref "R47") (pin "2") (pinfunction "2_2") (pintype "input"))
      (node (ref "U1") (pin "29") (pinfunction "IO36_29") (pintype "unspecified"))
    )
    (net (code "4") (name "/BTN3") (class "Default")
      (node (ref "R48") (pin "2") (pinfunction "2_2") (pintype "input"))
      (node (ref "U1") (pin "30") (pinfunction "IO37_30") (pintype "unspecified"))
    )
    (net (code "5") (name "/BTN4") (class "Default")
      (node (ref "R42") (pin "2") (pinfunction "2_2") (pintype "input"))
      (node (ref "U1") (pin "31") (pinfunction "IO38_31") (pintype "unspecified"))
    )
    (net (code "6") (name "/BTN5") (class "Default")
      (node (ref "R45") (pin "2") (pinfunction "2_2") (pintype "input"))
      (node (ref "U1") (pin "32") (pinfunction "IO39_32") (pintype "unspecified"))
    )
    (net (code "7") (name "/BTN6") (class "Default")
      (node (ref "R43") (pin "2") (pinfunction "2_2") (pintype "input"))
      (node (ref "U1") (pin "33") (pinfunction "IO40_33") (pintype "unspecified"))
    )
    (net (code "8") (name "/BTN7") (class "Default")
      (node (ref "R41") (pin "2") (pinfunction "2_2") (pintype "input"))
      (node (ref "U1") (pin "34") (pinfunction "IO41_34") (pintype "unspecified"))
    )
    (net (code "9") (name "/BTN8") (class "Default")
      (node (ref "R46") (pin "2") (pinfunction "2_2") (pintype "input"))
      (node (ref "U1") (pin "35") (pinfunction "IO42_35") (pintype "unspecified"))
    )
    (net (code "10") (name "/OUT1") (class "Default")
      (node (ref "C8") (pin "2") (pinfunction "2_2") (pintype "unspecified"))
      (node (ref "CN3") (pin "A1") (pinfunction "A1_A1") (pintype "unspecified"))
      (node (ref "R28") (pin "2") (pinfunction "2_2") (pintype "input"))
      (node (ref "U2") (pin "12") (pinfunction "OUT0_12") (pintype "input"))
      (node (ref "U2") (pin "13") (pinfunction "OUT0_13") (pintype "input"))
      (node (ref "U2") (pin "14") (pinfunction "OUT0_14") (pintype "input"))
    )
    (net (code "11") (name "/OUT2") (class "Default")
      (node (ref "C10") (pin "2") (pinfunction "2_2") (pintype "unspecified"))
      (node (ref "CN3") (pin "A2") (pinfunction "A2_A2") (pintype "unspecified"))
      (node (ref "R29") (pin "2") (pinfunction "2_2") (pintype "input"))
      (node (ref "U2") (pin "10") (pinfunction "OUT1_10") (pintype "input"))
      (node (ref "U2") (pin "8") (pinfunction "OUT1_8") (pintype "input"))
      (node (ref "U2") (pin "9") (pinfunction "OUT1_9") (pintype "input"))
    )
    (net (code "12") (name "/OUT3") (class "Default")
      (node (ref "C9") (pin "2") (pinfunction "2_2") (pintype "unspecified"))
      (node (ref "CN3") (pin "A3") (pinfunction "A3_A3") (pintype "unspecified"))
      (node (ref "R30") (pin "2") (pinfunction "2_2") (pintype "input"))
      (node (ref "U3") (pin "12") (pinfunction "OUT0_12") (pintype "input"))
      (node (ref "U3") (pin "13") (pinfunction "OUT0_13") (pintype "input"))
      (node (ref "U3") (pin "14") (pinfunction "OUT0_14") (pintype "input"))
    )
    (net (code "13") (name "/OUT4") (class "Default")
      (node (ref "C11") (pin "2") (pinfunction "2_2") (pintype "unspecified"))
      (node (ref "CN3") (pin "A4") (pinfunction "A4_A4") (pintype "unspecified"))
      (node (ref "R31") (pin "2") (pinfunction "2_2") (pintype "input"))
      (node (ref "U3") (pin "10") (pinfunction "OUT1_10") (pintype "input"))
      (node (ref "U3") (pin "8") (pinfunction "OUT1_8") (pintype "input"))
      (node (ref "U3") (pin "9") (pinfunction "OUT1_9") (pintype "input"))
    )
    (net (code "14") (name "/OUT5") (class "Default")
      (node (ref "C14") (pin "2") (pinfunction "2_2") (pintype "unspecified"))
      (node (ref "CN3") (pin "A5") (pinfunction "A5_A5") (pintype "unspecified"))
      (node (ref "R32") (pin "2") (pinfunction "2_2") (pintype "input"))
      (node (ref "U4") (pin "12") (pinfunction "OUT0_12") (pintype "input"))
      (node (ref "U4") (pin "13") (pinfunction "OUT0_13") (pintype "input"))
      (node (ref "U4") (pin "14") (pinfunction "OUT0_14") (pintype "input"))
    )
    (net (code "15") (name "/OUT6") (class "Default")
      (node (ref "C16") (pin "2") (pinfunction "2_2") (pintype "unspecified"))
      (node (ref "CN3") (pin "A6") (pinfunction "A6_A6") (pintype "unspecified"))
      (node (ref "R33") (pin "2") (pinfunction "2_2") (pintype "input"))
      (node (ref "U4") (pin "10") (pinfunction "OUT1_10") (pintype "input"))
      (node (ref "U4") (pin "8") (pinfunction "OUT1_8") (pintype "input"))
      (node (ref "U4") (pin "9") (pinfunction "OUT1_9") (pintype "input"))
    )
    (net (code "16") (name "/OUT7") (class "Default")
      (node (ref "C15") (pin "2") (pinfunction "2_2") (pintype "unspecified"))
      (node (ref "CN3") (pin "A7") (pinfunction "A7_A7") (pintype "unspecified"))
      (node (ref "R34") (pin "2") (pinfunction "2_2") (pintype "input"))
      (node (ref "U5") (pin "12") (pinfunction "OUT0_12") (pintype "input"))
      (node (ref "U5") (pin "13") (pinfunction "OUT0_13") (pintype "input"))
      (node (ref "U5") (pin "14") (pinfunction "OUT0_14") (pintype "input"))
    )
    (net (code "17") (name "/OUT8") (class "Default")
      (node (ref "C17") (pin "2") (pinfunction "2_2") (pintype "unspecified"))
      (node (ref "CN3") (pin "A8") (pinfunction "A8_A8") (pintype "unspecified"))
      (node (ref "R35") (pin "2") (pinfunction "2_2") (pintype "input"))
      (node (ref "U5") (pin "10") (pinfunction "OUT1_10") (pintype "input"))
      (node (ref "U5") (pin "8") (pinfunction "OUT1_8") (pintype "input"))
      (node (ref "U5") (pin "9") (pinfunction "OUT1_9") (pintype "input"))
    )
    (net (code "18") (name "/OUT9") (class "Default")
      (node (ref "C20") (pin "2") (pinfunction "2_2") (pintype "unspecified"))
      (node (ref "CN3") (pin "B5") (pinfunction "B5_B5") (pintype "unspecified"))
      (node (ref "R36") (pin "2") (pinfunction "2_2") (pintype "input"))
      (node (ref "U6") (pin "12") (pinfunction "OUT0_12") (pintype "input"))
      (node (ref "U6") (pin "13") (pinfunction "OUT0_13") (pintype "input"))
      (node (ref "U6") (pin "14") (pinfunction "OUT0_14") (pintype "input"))
    )
    (net (code "19") (name "/OUT10") (class "Default")
      (node (ref "C22") (pin "2") (pinfunction "2_2") (pintype "unspecified"))
      (node (ref "CN3") (pin "B6") (pinfunction "B6_B6") (pintype "unspecified"))
      (node (ref "R37") (pin "2") (pinfunction "2_2") (pintype "input"))
      (node (ref "U6") (pin "10") (pinfunction "OUT1_10") (pintype "input"))
      (node (ref "U6") (pin "8") (pinfunction "OUT1_8") (pintype "input"))
      (node (ref "U6") (pin "9") (pinfunction "OUT1_9") (pintype "input"))
    )
    (net (code "20") (name "/OUT11") (class "Default")
      (node (ref "C21") (pin "2") (pinfunction "2_2") (pintype "unspecified"))
      (node (ref "CN3") (pin "B7") (pinfunction "B7_B7") (pintype "unspecified"))
      (node (ref "R38") (pin "2") (pinfunction "2_2") (pintype "input"))
      (node (ref "U7") (pin "12") (pinfunction "OUT0_12") (pintype "input"))
      (node (ref "U7") (pin "13") (pinfunction "OUT0_13") (pintype "input"))
      (node (ref "U7") (pin "14") (pinfunction "OUT0_14") (pintype "input"))
    )
    (net (code "21") (name "/OUT12") (class "Default")
      (node (ref "C23") (pin "2") (pinfunction "2_2") (pintype "unspecified"))
      (node (ref "CN3") (pin "B8") (pinfunction "B8_B8") (pintype "unspecified"))
      (node (ref "R39") (pin "2") (pinfunction "2_2") (pintype "input"))
      (node (ref "U7") (pin "10") (pinfunction "OUT1_10") (pintype "input"))
      (node (ref "U7") (pin "8") (pinfunction "OUT1_8") (pintype "input"))
      (node (ref "U7") (pin "9") (pinfunction "OUT1_9") (pintype "input"))
    )
    (net (code "22") (name "/PROFET_DEN1") (class "Default")
      (node (ref "R6") (pin "1") (pinfunction "1_1") (pintype "input"))
      (node (ref "U1") (pin "23") (pinfunction "IO21_23") (pintype "unspecified"))
    )
    (net (code "23") (name "/PROFET_DEN2") (class "Default")
      (node (ref "R7") (pin "1") (pinfunction "1_1") (pintype "input"))
      (node (ref "U1") (pin "20") (pinfunction "IO12_20") (pintype "unspecified"))
    )
    (net (code "24") (name "/PROFET_DEN3") (class "Default")
      (node (ref "R14") (pin "1") (pinfunction "1_1") (pintype "input"))
      (node (ref "U1") (pin "16") (pinfunction "IO46_16") (pintype "unspecified"))
    )
    (net (code "25") (name "/PROFET_DEN4") (class "Default")
      (node (ref "R15") (pin "1") (pinfunction "1_1") (pintype "input"))
      (node (ref "U1") (pin "11") (pinfunction "IO18_11") (pintype "unspecified"))
    )
    (net (code "26") (name "/PROFET_DEN5") (class "Default")
      (node (ref "R22") (pin "1") (pinfunction "1_1") (pintype "input"))
      (node (ref "U1") (pin "8") (pinfunction "IO15_8") (pintype "unspecified"))
    )
    (net (code "27") (name "/PROFET_DEN6") (class "Default")
      (node (ref "R23") (pin "1") (pinfunction "1_1") (pintype "input"))
      (node (ref "U1") (pin "5") (pinfunction "IO5_5") (pintype "unspecified"))
    )
    (net (code "28") (name "/PROFET_DSEL") (class "Default")
      (node (ref "R16") (pin "1") (pinfunction "1_1") (pintype "input"))
      (node (ref "R17") (pin "1") (pinfunction "1_1") (pintype "input"))
      (node (ref "R24") (pin "1") (pinfunction "1_1") (pintype "input"))
      (node (ref "R25") (pin "1") (pinfunction "1_1") (pintype "input"))
      (node (ref "R8") (pin "1") (pinfunction "1_1") (pintype "input"))
      (node (ref "R9") (pin "1") (pinfunction "1_1") (pintype "input"))
      (node (ref "U1") (pin "25") (pinfunction "IO48_25") (pintype "unspecified"))
    )
    (net (code "29") (name "/PROFET_IN1") (class "Default")
      (node (ref "R4") (pin "1") (pinfunction "1_1") (pintype "input"))
      (node (ref "U1") (pin "24") (pinfunction "IO47_24") (pintype "unspecified"))
    )
    (net (code "30") (name "/PROFET_IN2") (class "Default")
      (node (ref "R10") (pin "1") (pinfunction "1_1") (pintype "input"))
      (node (ref "U1") (pin "22") (pinfunction "IO14_22") (pintype "unspecified"))
    )
    (net (code "31") (name "/PROFET_IN3") (class "Default")
      (node (ref "R5") (pin "1") (pinfunction "1_1") (pintype "input"))
      (node (ref "U1") (pin "21") (pinfunction "IO13_21") (pintype "unspecified"))
    )
    (net (code "32") (name "/PROFET_IN4") (class "Default")
      (node (ref "R11") (pin "1") (pinfunction "1_1") (pintype "input"))
      (node (ref "U1") (pin "19") (pinfunction "IO11_19") (pintype "unspecified"))
    )
    (net (code "33") (name "/PROFET_IN5") (class "Default")
      (node (ref "R12") (pin "1") (pinfunction "1_1") (pintype "input"))
      (node (ref "U1") (pin "18") (pinfunction "IO10_18") (pintype "unspecified"))
    )
    (net (code "34") (name "/PROFET_IN6") (class "Default")
      (node (ref "R18") (pin "1") (pinfunction "1_1") (pintype "input"))
      (node (ref "U1") (pin "15") (pinfunction "IO3_15") (pintype "unspecified"))
    )
    (net (code "35") (name "/PROFET_IN7") (class "Default")
      (node (ref "R13") (pin "1") (pinfunction "1_1") (pintype "input"))
      (node (ref "U1") (pin "12") (pinfunction "IO8_12") (pintype "unspecified"))
    )
    (net (code "36") (name "/PROFET_IN8") (class "Default")
      (node (ref "R19") (pin "1") (pinfunction "1_1") (pintype "input"))
      (node (ref "U1") (pin "10") (pinfunction "IO17_10") (pintype "unspecified"))
    )
    (net (code "37") (name "/PROFET_IN9") (class "Default")
      (node (ref "R20") (pin "1") (pinfunction "1_1") (pintype "input"))
      (node (ref "U1") (pin "9") (pinfunction "IO16_9") (pintype "unspecified"))
    )
    (net (code "38") (name "/PROFET_IN10") (class "Default")
      (node (ref "R26") (pin "1") (pinfunction "1_1") (pintype "input"))
      (node (ref "U1") (pin "7") (pinfunction "IO7_7") (pintype "unspecified"))
    )
    (net (code "39") (name "/PROFET_IN11") (class "Default")
      (node (ref "R21") (pin "1") (pinfunction "1_1") (pintype "input"))
      (node (ref "U1") (pin "6") (pinfunction "IO6_6") (pintype "unspecified"))
    )
    (net (code "40") (name "/PROFET_IN12") (class "Default")
      (node (ref "R27") (pin "1") (pinfunction "1_1") (pintype "input"))
      (node (ref "U1") (pin "4") (pinfunction "IO4_4") (pintype "unspecified"))
    )
    (net (code "41") (name "/PROFET_IS") (class "Default")
      (node (ref "C4") (pin "2") (pinfunction "2_2") (pintype "input"))
      (node (ref "R2") (pin "2") (pinfunction "2_2") (pintype "input"))
      (node (ref "R3") (pin "2") (pinfunction "2_2") (pintype "input"))
      (node (ref "U2") (pin "4") (pinfunction "IS_4") (pintype "input"))
      (node (ref "U3") (pin "4") (pinfunction "IS_4") (pintype "input"))
      (node (ref "U4") (pin "4") (pinfunction "IS_4") (pintype "input"))
      (node (ref "U5") (pin "4") (pinfunction "IS_4") (pintype "input"))
      (node (ref "U6") (pin "4") (pinfunction "IS_4") (pintype "input"))
      (node (ref "U7") (pin "4") (pinfunction "IS_4") (pintype "input"))
    )
    (net (code "42") (name "/UART_RX") (class "Default")
      (node (ref "H1") (pin "2") (pinfunction "2_2") (pintype "unspecified"))
      (node (ref "U1") (pin "36") (pinfunction "RXD0_36") (pintype "unspecified"))
    )
    (net (code "43") (name "/UART_TX") (class "Default")
      (node (ref "H1") (pin "1") (pinfunction "1_1") (pintype "unspecified"))
      (node (ref "U1") (pin "37") (pinfunction "TXD0_37") (pintype "unspecified"))
    )
    (net (code "44") (name "/VBAT_PROT") (class "Default")
      (node (ref "C12") (pin "1") (pinfunction "1_1") (pintype "unspecified"))
      (node (ref "C13") (pin "1") (pinfunction "1_1") (pintype "unspecified"))
      (node (ref "C18") (pin "1") (pinfunction "1_1") (pintype "unspecified"))
      (node (ref "C19") (pin "1") (pinfunction "1_1") (pintype "unspecified"))
      (node (ref "C32") (pin "2") (pinfunction "2_2") (pintype "input"))
      (node (ref "C6") (pin "1") (pinfunction "1_1") (pintype "unspecified"))
      (node (ref "C7") (pin "1") (pinfunction "1_1") (pintype "unspecified"))
      (node (ref "CN3") (pin "B1") (pinfunction "B1_B1") (pintype "unspecified"))
      (node (ref "CN3") (pin "B2") (pinfunction "B2_B2") (pintype "unspecified"))
      (node (ref "D1") (pin "1") (pinfunction "K_1") (pintype "unspecified"))
      (node (ref "D2") (pin "2") (pinfunction "A_2") (pintype "unspecified"))
      (node (ref "R58") (pin "2") (pinfunction "2_2") (pintype "input"))
      (node (ref "U2") (pin "15") (pinfunction "VS_15") (pintype "input"))
      (node (ref "U3") (pin "15") (pinfunction "VS_15") (pintype "input"))
      (node (ref "U4") (pin "15") (pinfunction "VS_15") (pintype "input"))
      (node (ref "U5") (pin "15") (pinfunction "VS_15") (pintype "input"))
      (node (ref "U6") (pin "15") (pinfunction "VS_15") (pintype "input"))
      (node (ref "U7") (pin "15") (pinfunction "VS_15") (pintype "input"))
      (node (ref "U9") (pin "1") (pinfunction "1_1") (pintype "input"))
    )
    (net (code "45") (name "/VSENSE_BAT") (class "Default")
      (node (ref "C5") (pin "2") (pinfunction "2_2") (pintype "unspecified"))
      (node (ref "R57") (pin "2") (pinfunction "2_2") (pintype "input"))
      (node (ref "R58") (pin "1") (pinfunction "1_1") (pintype "input"))
      (node (ref "U1") (pin "39") (pinfunction "IO1_39") (pintype "unspecified"))
    )
    (net (code "46") (name "GND") (class "Default")
      (node (ref "C1") (pin "2") (pinfunction "2_2") (pintype "unspecified"))
      (node (ref "C10") (pin "1") (pinfunction "1_1") (pintype "unspecified"))
      (node (ref "C11") (pin "1") (pinfunction "1_1") (pintype "unspecified"))
      (node (ref "C12") (pin "2") (pinfunction "2_2") (pintype "unspecified"))
      (node (ref "C13") (pin "2") (pinfunction "2_2") (pintype "unspecified"))
      (node (ref "C14") (pin "1") (pinfunction "1_1") (pintype "unspecified"))
      (node (ref "C15") (pin "1") (pinfunction "1_1") (pintype "unspecified"))
      (node (ref "C16") (pin "1") (pinfunction "1_1") (pintype "unspecified"))
      (node (ref "C17") (pin "1") (pinfunction "1_1") (pintype "unspecified"))
      (node (ref "C18") (pin "2") (pinfunction "2_2") (pintype "unspecified"))
      (node (ref "C19") (pin "2") (pinfunction "2_2") (pintype "unspecified"))
      (node (ref "C2") (pin "2") (pinfunction "2_2") (pintype "unspecified"))
      (node (ref "C20") (pin "1") (pinfunction "1_1") (pintype "unspecified"))
      (node (ref "C21") (pin "1") (pinfunction "1_1") (pintype "unspecified"))
      (node (ref "C22") (pin "1") (pinfunction "1_1") (pintype "unspecified"))
      (node (ref "C23") (pin "1") (pinfunction "1_1") (pintype "unspecified"))
      (node (ref "C24") (pin "2") (pinfunction "2_2") (pintype "unspecified"))
      (node (ref "C25") (pin "2") (pinfunction "2_2") (pintype "unspecified"))
      (node (ref "C26") (pin "2") (pinfunction "2_2") (pintype "unspecified"))
      (node (ref "C27") (pin "2") (pinfunction "2_2") (pintype "unspecified"))
      (node (ref "C28") (pin "2") (pinfunction "2_2") (pintype "unspecified"))
      (node (ref "C29") (pin "2") (pinfunction "2_2") (pintype "unspecified"))
      (node (ref "C3") (pin "1") (pinfunction "1_1") (pintype "unspecified"))
      (node (ref "C30") (pin "2") (pinfunction "2_2") (pintype "unspecified"))
      (node (ref "C31") (pin "2") (pinfunction "2_2") (pintype "unspecified"))
      (node (ref "C32") (pin "1") (pinfunction "1_1") (pintype "input"))
      (node (ref "C33") (pin "1") (pinfunction "1_1") (pintype "unspecified"))
      (node (ref "C34") (pin "1") (pinfunction "1_1") (pintype "input"))
      (node (ref "C4") (pin "1") (pinfunction "1_1") (pintype "input"))
      (node (ref "C5") (pin "1") (pinfunction "1_1") (pintype "unspecified"))
      (node (ref "C6") (pin "2") (pinfunction "2_2") (pintype "unspecified"))
      (node (ref "C7") (pin "2") (pinfunction "2_2") (pintype "unspecified"))
      (node (ref "C8") (pin "1") (pinfunction "1_1") (pintype "unspecified"))
      (node (ref "C9") (pin "1") (pinfunction "1_1") (pintype "unspecified"))
      (node (ref "CN3") (pin "B3") (pinfunction "B3_B3") (pintype "unspecified"))
      (node (ref "CN3") (pin "B4") (pinfunction "B4_B4") (pintype "unspecified"))
      (node (ref "D1") (pin "2") (pinfunction "A_2") (pintype "unspecified"))
      (node (ref "H1") (pin "3") (pinfunction "3_3") (pintype "unspecified"))
      (node (ref "LED1") (pin "2") (pinfunction "K_2") (pintype "unspecified"))
      (node (ref "LED10") (pin "2") (pinfunction "K_2") (pintype "unspecified"))
      (node (ref "LED11") (pin "2") (pinfunction "K_2") (pintype "unspecified"))
      (node (ref "LED12") (pin "2") (pinfunction "K_2") (pintype "unspecified"))
      (node (ref "LED13") (pin "2") (pinfunction "K_2") (pintype "unspecified"))
      (node (ref "LED2") (pin "2") (pinfunction "K_2") (pintype "unspecified"))
      (node (ref "LED3") (pin "2") (pinfunction "K_2") (pintype "unspecified"))
      (node (ref "LED4") (pin "2") (pinfunction "K_2") (pintype "unspecified"))
      (node (ref "LED5") (pin "2") (pinfunction "K_2") (pintype "unspecified"))
      (node (ref "LED6") (pin "2") (pinfunction "K_2") (pintype "unspecified"))
      (node (ref "LED7") (pin "2") (pinfunction "K_2") (pintype "unspecified"))
      (node (ref "LED8") (pin "2") (pinfunction "K_2") (pintype "unspecified"))
      (node (ref "LED9") (pin "2") (pinfunction "K_2") (pintype "unspecified"))
      (node (ref "R3") (pin "1") (pinfunction "1_1") (pintype "input"))
      (node (ref "R57") (pin "1") (pinfunction "1_1") (pintype "input"))
      (node (ref "SW1") (pin "3") (pinfunction "C_3") (pintype "unspecified"))
      (node (ref "SW2") (pin "3") (pinfunction "C_3") (pintype "unspecified"))
      (node (ref "U1") (pin "1") (pinfunction "GND_1") (pintype "unspecified"))
      (node (ref "U1") (pin "40") (pinfunction "GND_40") (pintype "unspecified"))
      (node (ref "U1") (pin "41") (pinfunction "GND_41") (pintype "unspecified"))
      (node (ref "U10") (pin "2") (pinfunction "GND_2") (pintype "unspecified"))
      (node (ref "U2") (pin "1") (pinfunction "GND_1") (pintype "input"))
      (node (ref "U3") (pin "1") (pinfunction "GND_1") (pintype "input"))
      (node (ref "U4") (pin "1") (pinfunction "GND_1") (pintype "input"))
      (node (ref "U5") (pin "1") (pinfunction "GND_1") (pintype "input"))
      (node (ref "U6") (pin "1") (pinfunction "GND_1") (pintype "input"))
      (node (ref "U7") (pin "1") (pinfunction "GND_1") (pintype "input"))
      (node (ref "U9") (pin "2") (pinfunction "2_2") (pintype "input"))
    )
    (net (code "47") (name "Net-(C24-Pad1)") (class "Default")
      (node (ref "C24") (pin "1") (pinfunction "1_1") (pintype "unspecified"))
      (node (ref "CN3") (pin "C6") (pinfunction "C6_C6") (pintype "unspecified"))
      (node (ref "R43") (pin "1") (pinfunction "1_1") (pintype "input"))
      (node (ref "R54") (pin "1") (pinfunction "1_1") (pintype "input"))
    )
    (net (code "48") (name "Net-(C25-Pad1)") (class "Default")
      (node (ref "C25") (pin "1") (pinfunction "1_1") (pintype "unspecified"))
      (node (ref "CN3") (pin "C5") (pinfunction "C5_C5") (pintype "unspecified"))
      (node (ref "R45") (pin "1") (pinfunction "1_1") (pintype "input"))
      (node (ref "R52") (pin "1") (pinfunction "1_1") (pintype "input"))
    )
    (net (code "49") (name "Net-(C26-Pad1)") (class "Default")
      (node (ref "C26") (pin "1") (pinfunction "1_1") (pintype "unspecified"))
      (node (ref "CN3") (pin "C4") (pinfunction "C4_C4") (pintype "unspecified"))
      (node (ref "R42") (pin "1") (pinfunction "1_1") (pintype "input"))
      (node (ref "R56") (pin "1") (pinfunction "1_1") (pintype "input"))
    )
    (net (code "50") (name "Net-(C27-Pad1)") (class "Default")
      (node (ref "C27") (pin "1") (pinfunction "1_1") (pintype "unspecified"))
      (node (ref "CN3") (pin "C8") (pinfunction "C8_C8") (pintype "unspecified"))
      (node (ref "R46") (pin "1") (pinfunction "1_1") (pintype "input"))
      (node (ref "R49") (pin "1") (pinfunction "1_1") (pintype "input"))
    )
    (net (code "51") (name "Net-(C28-Pad1)") (class "Default")
      (node (ref "C28") (pin "1") (pinfunction "1_1") (pintype "unspecified"))
      (node (ref "CN3") (pin "C2") (pinfunction "C2_C2") (pintype "unspecified"))
      (node (ref "R44") (pin "1") (pinfunction "1_1") (pintype "input"))
      (node (ref "R50") (pin "1") (pinfunction "1_1") (pintype "input"))
    )
    (net (code "52") (name "Net-(C29-Pad1)") (class "Default")
      (node (ref "C29") (pin "1") (pinfunction "1_1") (pintype "unspecified"))
      (node (ref "CN3") (pin "C7") (pinfunction "C7_C7") (pintype "unspecified"))
      (node (ref "R41") (pin "1") (pinfunction "1_1") (pintype "input"))
      (node (ref "R55") (pin "1") (pinfunction "1_1") (pintype "input"))
    )
    (net (code "53") (name "Net-(C30-Pad1)") (class "Default")
      (node (ref "C30") (pin "1") (pinfunction "1_1") (pintype "unspecified"))
      (node (ref "CN3") (pin "C3") (pinfunction "C3_C3") (pintype "unspecified"))
      (node (ref "R48") (pin "1") (pinfunction "1_1") (pintype "input"))
      (node (ref "R53") (pin "1") (pinfunction "1_1") (pintype "input"))
    )
    (net (code "54") (name "Net-(C31-Pad1)") (class "Default")
      (node (ref "C31") (pin "1") (pinfunction "1_1") (pintype "unspecified"))
      (node (ref "CN3") (pin "C1") (pinfunction "C1_C1") (pintype "unspecified"))
      (node (ref "R47") (pin "1") (pinfunction "1_1") (pintype "input"))
      (node (ref "R51") (pin "1") (pinfunction "1_1") (pintype "input"))
    )
    (net (code "55") (name "Net-(D2-K)") (class "Default")
      (node (ref "C34") (pin "2") (pinfunction "2_2") (pintype "input"))
      (node (ref "D2") (pin "1") (pinfunction "K_1") (pintype "unspecified"))
      (node (ref "U10") (pin "1") (pinfunction "VIN_1") (pintype "unspecified"))
    )
    (net (code "56") (name "Net-(LED1-A)") (class "Default")
      (node (ref "LED1") (pin "1") (pinfunction "A_1") (pintype "unspecified"))
      (node (ref "R28") (pin "1") (pinfunction "1_1") (pintype "input"))
    )
    (net (code "57") (name "Net-(LED2-A)") (class "Default")
      (node (ref "LED2") (pin "1") (pinfunction "A_1") (pintype "unspecified"))
      (node (ref "R29") (pin "1") (pinfunction "1_1") (pintype "input"))
    )
    (net (code "58") (name "Net-(LED3-A)") (class "Default")
      (node (ref "LED3") (pin "1") (pinfunction "A_1") (pintype "unspecified"))
      (node (ref "R30") (pin "1") (pinfunction "1_1") (pintype "input"))
    )
    (net (code "59") (name "Net-(LED4-A)") (class "Default")
      (node (ref "LED4") (pin "1") (pinfunction "A_1") (pintype "unspecified"))
      (node (ref "R31") (pin "1") (pinfunction "1_1") (pintype "input"))
    )
    (net (code "60") (name "Net-(LED5-A)") (class "Default")
      (node (ref "LED5") (pin "1") (pinfunction "A_1") (pintype "unspecified"))
      (node (ref "R32") (pin "1") (pinfunction "1_1") (pintype "input"))
    )
    (net (code "61") (name "Net-(LED6-A)") (class "Default")
      (node (ref "LED6") (pin "1") (pinfunction "A_1") (pintype "unspecified"))
      (node (ref "R33") (pin "1") (pinfunction "1_1") (pintype "input"))
    )
    (net (code "62") (name "Net-(LED7-A)") (class "Default")
      (node (ref "LED7") (pin "1") (pinfunction "A_1") (pintype "unspecified"))
      (node (ref "R34") (pin "1") (pinfunction "1_1") (pintype "input"))
    )
    (net (code "63") (name "Net-(LED8-A)") (class "Default")
      (node (ref "LED8") (pin "1") (pinfunction "A_1") (pintype "unspecified"))
      (node (ref "R35") (pin "1") (pinfunction "1_1") (pintype "input"))
    )
    (net (code "64") (name "Net-(LED9-A)") (class "Default")
      (node (ref "LED9") (pin "1") (pinfunction "A_1") (pintype "unspecified"))
      (node (ref "R36") (pin "1") (pinfunction "1_1") (pintype "input"))
    )
    (net (code "65") (name "Net-(LED10-A)") (class "Default")
      (node (ref "LED10") (pin "1") (pinfunction "A_1") (pintype "unspecified"))
      (node (ref "R37") (pin "1") (pinfunction "1_1") (pintype "input"))
    )
    (net (code "66") (name "Net-(LED11-A)") (class "Default")
      (node (ref "LED11") (pin "1") (pinfunction "A_1") (pintype "unspecified"))
      (node (ref "R38") (pin "1") (pinfunction "1_1") (pintype "input"))
    )
    (net (code "67") (name "Net-(LED12-A)") (class "Default")
      (node (ref "LED12") (pin "1") (pinfunction "A_1") (pintype "unspecified"))
      (node (ref "R39") (pin "1") (pinfunction "1_1") (pintype "input"))
    )
    (net (code "68") (name "Net-(LED13-A)") (class "Default")
      (node (ref "LED13") (pin "1") (pinfunction "A_1") (pintype "unspecified"))
      (node (ref "R40") (pin "1") (pinfunction "1_1") (pintype "input"))
    )
    (net (code "69") (name "Net-(SW1-B)") (class "Default")
      (node (ref "C3") (pin "2") (pinfunction "2_2") (pintype "unspecified"))
      (node (ref "R1") (pin "2") (pinfunction "2_2") (pintype "input"))
      (node (ref "SW1") (pin "2") (pinfunction "B_2") (pintype "unspecified"))
      (node (ref "U1") (pin "3") (pinfunction "EN_3") (pintype "unspecified"))
    )
    (net (code "70") (name "Net-(SW2-A)") (class "Default")
      (node (ref "SW2") (pin "1") (pinfunction "A_1") (pintype "unspecified"))
      (node (ref "U1") (pin "27") (pinfunction "IO0_27") (pintype "unspecified"))
    )
    (net (code "71") (name "Net-(U1-IO9)") (class "Default")
      (node (ref "R2") (pin "1") (pinfunction "1_1") (pintype "input"))
      (node (ref "U1") (pin "17") (pinfunction "IO9_17") (pintype "unspecified"))
    )
    (net (code "72") (name "Net-(U2-DEN)") (class "Default")
      (node (ref "R6") (pin "2") (pinfunction "2_2") (pintype "input"))
      (node (ref "U2") (pin "3") (pinfunction "DEN_3") (pintype "input"))
    )
    (net (code "73") (name "Net-(U2-DSEL)") (class "Default")
      (node (ref "R8") (pin "2") (pinfunction "2_2") (pintype "input"))
      (node (ref "U2") (pin "5") (pinfunction "DSEL_5") (pintype "input"))
    )
    (net (code "74") (name "Net-(U2-IN0)") (class "Default")
      (node (ref "R4") (pin "2") (pinfunction "2_2") (pintype "input"))
      (node (ref "U2") (pin "2") (pinfunction "IN0_2") (pintype "input"))
    )
    (net (code "75") (name "Net-(U2-IN1)") (class "Default")
      (node (ref "R10") (pin "2") (pinfunction "2_2") (pintype "input"))
      (node (ref "U2") (pin "6") (pinfunction "IN1_6") (pintype "input"))
    )
    (net (code "76") (name "Net-(U3-DEN)") (class "Default")
      (node (ref "R7") (pin "2") (pinfunction "2_2") (pintype "input"))
      (node (ref "U3") (pin "3") (pinfunction "DEN_3") (pintype "input"))
    )
    (net (code "77") (name "Net-(U3-DSEL)") (class "Default")
      (node (ref "R9") (pin "2") (pinfunction "2_2") (pintype "input"))
      (node (ref "U3") (pin "5") (pinfunction "DSEL_5") (pintype "input"))
    )
    (net (code "78") (name "Net-(U3-IN0)") (class "Default")
      (node (ref "R5") (pin "2") (pinfunction "2_2") (pintype "input"))
      (node (ref "U3") (pin "2") (pinfunction "IN0_2") (pintype "input"))
    )
    (net (code "79") (name "Net-(U3-IN1)") (class "Default")
      (node (ref "R11") (pin "2") (pinfunction "2_2") (pintype "input"))
      (node (ref "U3") (pin "6") (pinfunction "IN1_6") (pintype "input"))
    )
    (net (code "80") (name "Net-(U4-DEN)") (class "Default")
      (node (ref "R14") (pin "2") (pinfunction "2_2") (pintype "input"))
      (node (ref "U4") (pin "3") (pinfunction "DEN_3") (pintype "input"))
    )
    (net (code "81") (name "Net-(U4-DSEL)") (class "Default")
      (node (ref "R16") (pin "2") (pinfunction "2_2") (pintype "input"))
      (node (ref "U4") (pin "5") (pinfunction "DSEL_5") (pintype "input"))
    )
    (net (code "82") (name "Net-(U4-IN0)") (class "Default")
      (node (ref "R12") (pin "2") (pinfunction "2_2") (pintype "input"))
      (node (ref "U4") (pin "2") (pinfunction "IN0_2") (pintype "input"))
    )
    (net (code "83") (name "Net-(U4-IN1)") (class "Default")
      (node (ref "R18") (pin "2") (pinfunction "2_2") (pintype "input"))
      (node (ref "U4") (pin "6") (pinfunction "IN1_6") (pintype "input"))
    )
    (net (code "84") (name "Net-(U5-DEN)") (class "Default")
      (node (ref "R15") (pin "2") (pinfunction "2_2") (pintype "input"))
      (node (ref "U5") (pin "3") (pinfunction "DEN_3") (pintype "input"))
    )
    (net (code "85") (name "Net-(U5-DSEL)") (class "Default")
      (node (ref "R17") (pin "2") (pinfunction "2_2") (pintype "input"))
      (node (ref "U5") (pin "5") (pinfunction "DSEL_5") (pintype "input"))
    )
    (net (code "86") (name "Net-(U5-IN0)") (class "Default")
      (node (ref "R13") (pin "2") (pinfunction "2_2") (pintype "input"))
      (node (ref "U5") (pin "2") (pinfunction "IN0_2") (pintype "input"))
    )
    (net (code "87") (name "Net-(U5-IN1)") (class "Default")
      (node (ref "R19") (pin "2") (pinfunction "2_2") (pintype "input"))
      (node (ref "U5") (pin "6") (pinfunction "IN1_6") (pintype "input"))
    )
    (net (code "88") (name "Net-(U6-DEN)") (class "Default")
      (node (ref "R22") (pin "2") (pinfunction "2_2") (pintype "input"))
      (node (ref "U6") (pin "3") (pinfunction "DEN_3") (pintype "input"))
    )
    (net (code "89") (name "Net-(U6-DSEL)") (class "Default")
      (node (ref "R24") (pin "2") (pinfunction "2_2") (pintype "input"))
      (node (ref "U6") (pin "5") (pinfunction "DSEL_5") (pintype "input"))
    )
    (net (code "90") (name "Net-(U6-IN0)") (class "Default")
      (node (ref "R20") (pin "2") (pinfunction "2_2") (pintype "input"))
      (node (ref "U6") (pin "2") (pinfunction "IN0_2") (pintype "input"))
    )
    (net (code "91") (name "Net-(U6-IN1)") (class "Default")
      (node (ref "R26") (pin "2") (pinfunction "2_2") (pintype "input"))
      (node (ref "U6") (pin "6") (pinfunction "IN1_6") (pintype "input"))
    )
    (net (code "92") (name "Net-(U7-DEN)") (class "Default")
      (node (ref "R23") (pin "2") (pinfunction "2_2") (pintype "input"))
      (node (ref "U7") (pin "3") (pinfunction "DEN_3") (pintype "input"))
    )
    (net (code "93") (name "Net-(U7-DSEL)") (class "Default")
      (node (ref "R25") (pin "2") (pinfunction "2_2") (pintype "input"))
      (node (ref "U7") (pin "5") (pinfunction "DSEL_5") (pintype "input"))
    )
    (net (code "94") (name "Net-(U7-IN0)") (class "Default")
      (node (ref "R21") (pin "2") (pinfunction "2_2") (pintype "input"))
      (node (ref "U7") (pin "2") (pinfunction "IN0_2") (pintype "input"))
    )
    (net (code "95") (name "Net-(U7-IN1)") (class "Default")
      (node (ref "R27") (pin "2") (pinfunction "2_2") (pintype "input"))
      (node (ref "U7") (pin "6") (pinfunction "IN1_6") (pintype "input"))
    )
    (net (code "96") (name "unconnected-(SCREW1-Pad1)") (class "Default")
      (node (ref "SCREW1") (pin "1") (pinfunction "1_1") (pintype "input"))
    )
    (net (code "97") (name "unconnected-(SCREW2-Pad1)") (class "Default")
      (node (ref "SCREW2") (pin "1") (pinfunction "1_1") (pintype "input"))
    )
    (net (code "98") (name "unconnected-(SCREW3-Pad1)") (class "Default")
      (node (ref "SCREW3") (pin "1") (pinfunction "1_1") (pintype "input"))
    )
    (net (code "99") (name "unconnected-(SCREW4-Pad1)") (class "Default")
      (node (ref "SCREW4") (pin "1") (pinfunction "1_1") (pintype "input"))
    )
    (net (code "100") (name "unconnected-(SW1-A-Pad1)") (class "Default")
      (node (ref "SW1") (pin "1") (pinfunction "A_1") (pintype "unspecified+no_connect"))
    )
    (net (code "101") (name "unconnected-(SW1-D-Pad4)") (class "Default")
      (node (ref "SW1") (pin "4") (pinfunction "D_4") (pintype "unspecified+no_connect"))
    )
    (net (code "102") (name "unconnected-(SW2-B-Pad2)") (class "Default")
      (node (ref "SW2") (pin "2") (pinfunction "B_2") (pintype "unspecified+no_connect"))
    )
    (net (code "103") (name "unconnected-(SW2-D-Pad4)") (class "Default")
      (node (ref "SW2") (pin "4") (pinfunction "D_4") (pintype "unspecified+no_connect"))
    )
    (net (code "104") (name "unconnected-(U1-IO2-Pad38)") (class "Default")
      (node (ref "U1") (pin "38") (pinfunction "IO2_38") (pintype "unspecified+no_connect"))
    )
    (net (code "105") (name "unconnected-(U1-IO19-Pad13)") (class "Default")
      (node (ref "U1") (pin "13") (pinfunction "IO19_13") (pintype "unspecified+no_connect"))
    )
    (net (code "106") (name "unconnected-(U1-IO20-Pad14)") (class "Default")
      (node (ref "U1") (pin "14") (pinfunction "IO20_14") (pintype "unspecified+no_connect"))
    )
    (net (code "107") (name "unconnected-(U1-IO45-Pad26)") (class "Default")
      (node (ref "U1") (pin "26") (pinfunction "IO45_26") (pintype "unspecified+no_connect"))
    )
    (net (code "108") (name "unconnected-(U2-n.c.-Pad7)") (class "Default")
      (node (ref "U2") (pin "7") (pinfunction "n.c._7") (pintype "input+no_connect"))
    )
    (net (code "109") (name "unconnected-(U2-n.c.-Pad11)") (class "Default")
      (node (ref "U2") (pin "11") (pinfunction "n.c._11") (pintype "input+no_connect"))
    )
    (net (code "110") (name "unconnected-(U3-n.c.-Pad7)") (class "Default")
      (node (ref "U3") (pin "7") (pinfunction "n.c._7") (pintype "input+no_connect"))
    )
    (net (code "111") (name "unconnected-(U3-n.c.-Pad11)") (class "Default")
      (node (ref "U3") (pin "11") (pinfunction "n.c._11") (pintype "input+no_connect"))
    )
    (net (code "112") (name "unconnected-(U4-n.c.-Pad7)") (class "Default")
      (node (ref "U4") (pin "7") (pinfunction "n.c._7") (pintype "input+no_connect"))
    )
    (net (code "113") (name "unconnected-(U4-n.c.-Pad11)") (class "Default")
      (node (ref "U4") (pin "11") (pinfunction "n.c._11") (pintype "input+no_connect"))
    )
    (net (code "114") (name "unconnected-(U5-n.c.-Pad7)") (class "Default")
      (node (ref "U5") (pin "7") (pinfunction "n.c._7") (pintype "input+no_connect"))
    )
    (net (code "115") (name "unconnected-(U5-n.c.-Pad11)") (class "Default")
      (node (ref "U5") (pin "11") (pinfunction "n.c._11") (pintype "input+no_connect"))
    )
    (net (code "116") (name "unconnected-(U6-n.c.-Pad7)") (class "Default")
      (node (ref "U6") (pin "7") (pinfunction "n.c._7") (pintype "input+no_connect"))
    )
    (net (code "117") (name "unconnected-(U6-n.c.-Pad11)") (class "Default")
      (node (ref "U6") (pin "11") (pinfunction "n.c._11") (pintype "input+no_connect"))
    )
    (net (code "118") (name "unconnected-(U7-n.c.-Pad7)") (class "Default")
      (node (ref "U7") (pin "7") (pinfunction "n.c._7") (pintype "input+no_connect"))
    )
    (net (code "119") (name "unconnected-(U7-n.c.-Pad11)") (class "Default")
      (node (ref "U7") (pin "11") (pinfunction "n.c._11") (pintype "input+no_connect"))
    )
  )
)
